# trackoon_solar.net
KiCad netlist of a schematic drawn in EAGLE
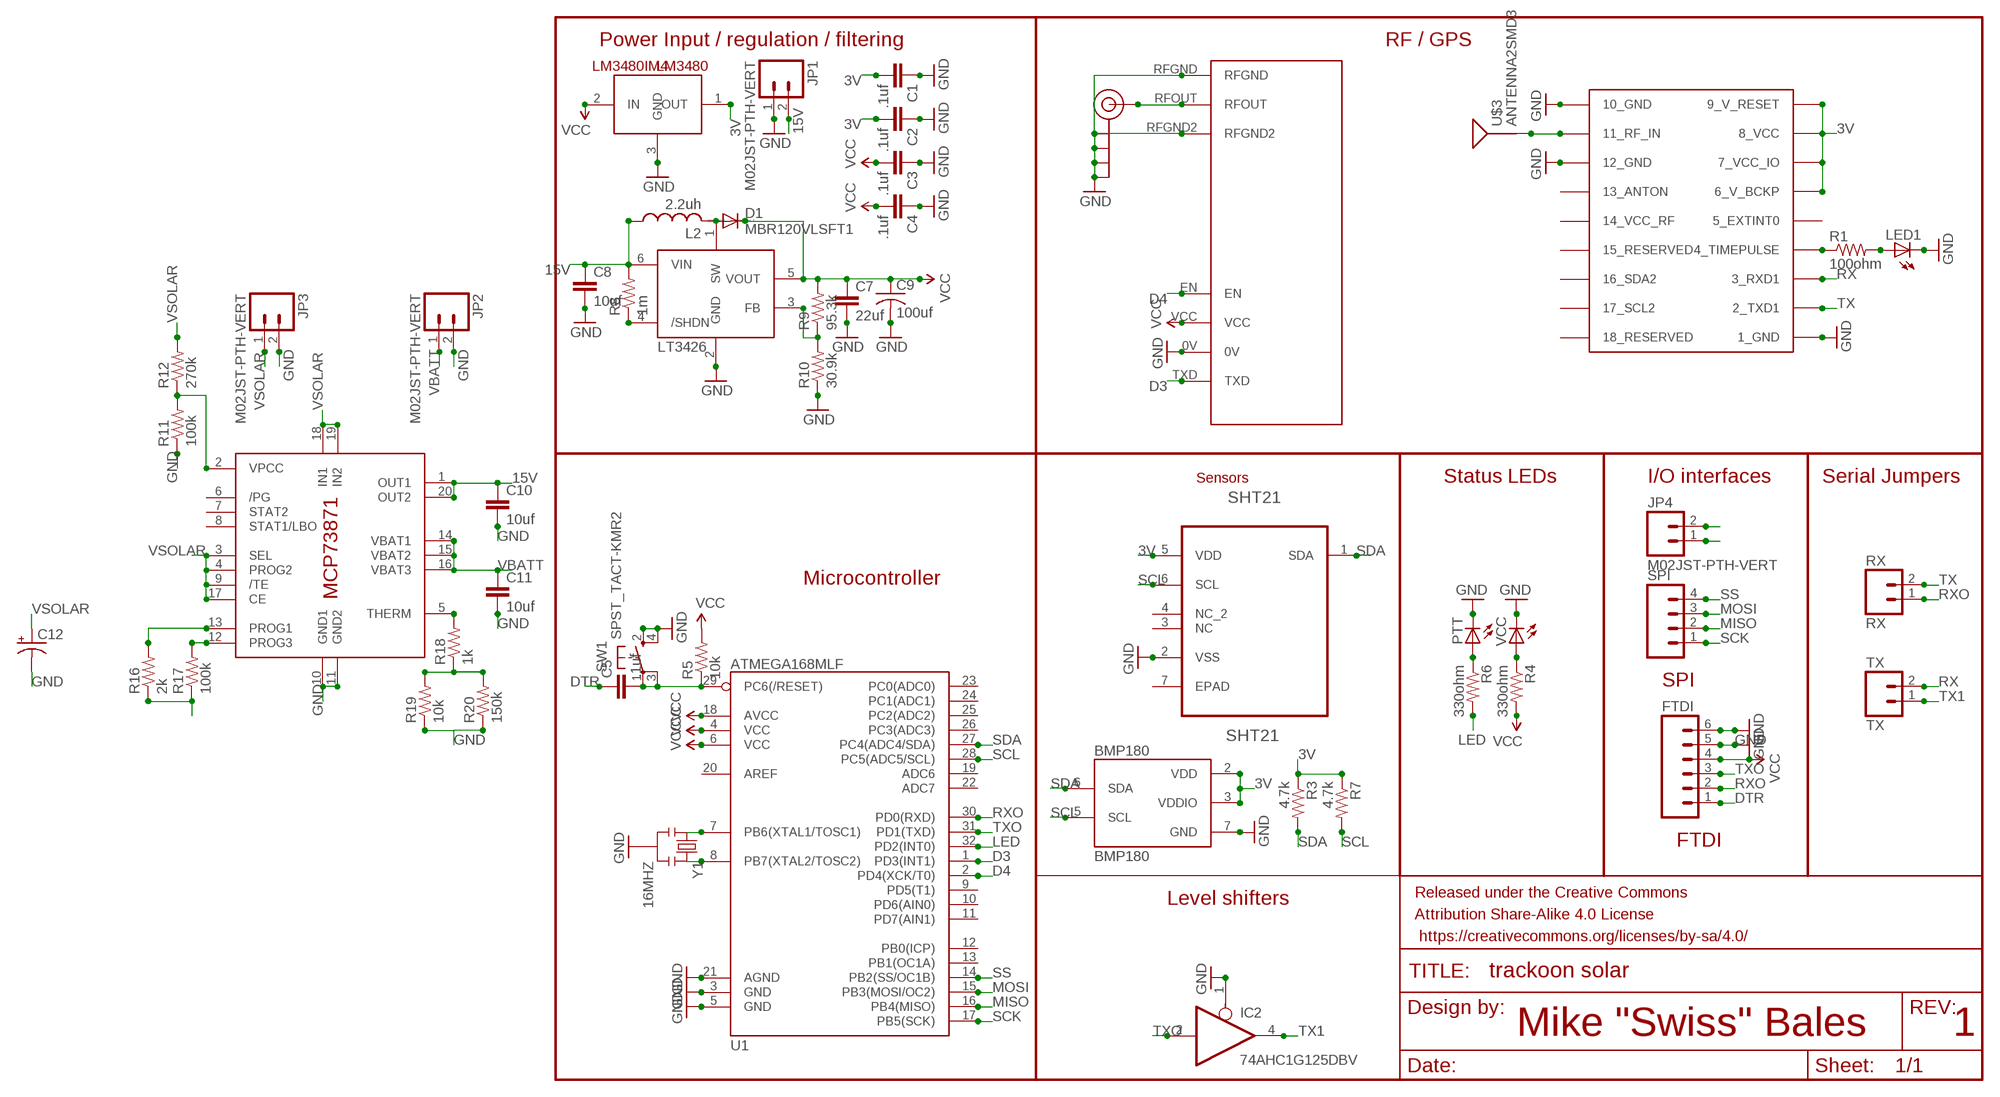
[diagram p0: schematic, sheet 1]

(export (version "E")
  (design (tool "Eeschema 10.0.6"))
  (components
    (comp (ref "BMP180")
      (value "BMP180")
      (footprint "eagle-import:BMP180")
      (libsource (lib "eagle-import") (part "BMP180"))
    )
    (comp (ref "C1")
      (value ".1uf")
      (footprint "eagle-import:0805")
      (libsource (lib "eagle-import") (part "CAP0805"))
    )
    (comp (ref "C2")
      (value ".1uf")
      (footprint "eagle-import:0805")
      (libsource (lib "eagle-import") (part "CAP0805"))
    )
    (comp (ref "C3")
      (value ".1uf")
      (footprint "eagle-import:0805")
      (libsource (lib "eagle-import") (part "CAP0805"))
    )
    (comp (ref "C4")
      (value ".1uf")
      (footprint "eagle-import:0805")
      (libsource (lib "eagle-import") (part "CAP0805"))
    )
    (comp (ref "C5")
      (value ".1uf")
      (footprint "eagle-import:0805")
      (libsource (lib "eagle-import") (part "CAP0805"))
    )
    (comp (ref "C7")
      (value "22uf")
      (footprint "eagle-import:0805")
      (libsource (lib "eagle-import") (part "CAP0805"))
    )
    (comp (ref "C8")
      (value "10uf")
      (footprint "eagle-import:0805")
      (libsource (lib "eagle-import") (part "CAP0805"))
    )
    (comp (ref "C9")
      (value "100uf")
      (footprint "eagle-import:C1206")
      (libsource (lib "eagle-import") (part "C-USC1206"))
    )
    (comp (ref "C10")
      (value "10uf")
      (footprint "eagle-import:0805")
      (libsource (lib "eagle-import") (part "CAP0805"))
    )
    (comp (ref "C11")
      (value "10uf")
      (footprint "eagle-import:0805")
      (libsource (lib "eagle-import") (part "CAP0805"))
    )
    (comp (ref "C12")
      (value "CPOL-US153CLV-1012")
      (footprint "eagle-import:153CLV-1012")
      (libsource (lib "eagle-import") (part "CPOL-US153CLV-1012"))
    )
    (comp (ref "D1")
      (value "MBR120VLSFT1")
      (footprint "eagle-import:SOD123")
      (libsource (lib "eagle-import") (part "DIODE-SOD123"))
    )
    (comp (ref "FRAME1")
      (value "FRAME-LETTER")
      (footprint "eagle-import:CREATIVE_COMMONS")
      (libsource (lib "eagle-import") (part "FRAME-LETTER"))
    )
    (comp (ref "FTDI")
      (value "M06NO_SILK_FEMALE_PTH")
      (footprint "eagle-import:1X06_NO_SILK")
      (libsource (lib "eagle-import") (part "M06NO_SILK_FEMALE_PTH"))
    )
    (comp (ref "IC1")
      (value "MCP73871")
      (footprint "eagle-import:QFN20")
      (libsource (lib "eagle-import") (part "MCP73871"))
    )
    (comp (ref "IC2")
      (value "74AHC1G125DBV")
      (footprint "eagle-import:SOT23-5")
      (libsource (lib "eagle-import") (part "741G125DBVAHC"))
    )
    (comp (ref "J$1")
      (value "SMA_EDGE")
      (footprint "eagle-import:SMA-EDGE")
      (libsource (lib "eagle-import") (part "SMA_EDGE"))
    )
    (comp (ref "JP1")
      (value "M02JST-PTH-VERT")
      (footprint "eagle-import:JST-2-PTH-VERT")
      (libsource (lib "eagle-import") (part "M02JST-PTH-VERT"))
    )
    (comp (ref "JP2")
      (value "M02JST-PTH-VERT")
      (footprint "eagle-import:JST-2-PTH-VERT")
      (libsource (lib "eagle-import") (part "M02JST-PTH-VERT"))
    )
    (comp (ref "JP3")
      (value "M02JST-PTH-VERT")
      (footprint "eagle-import:JST-2-PTH-VERT")
      (libsource (lib "eagle-import") (part "M02JST-PTH-VERT"))
    )
    (comp (ref "JP4")
      (value "M02JST-PTH-VERT")
      (footprint "eagle-import:JST-2-PTH-VERT")
      (libsource (lib "eagle-import") (part "M02JST-PTH-VERT"))
    )
    (comp (ref "L2")
      (value "2.2uh")
      (footprint "eagle-import:L1812")
      (libsource (lib "eagle-import") (part "L-USL1812"))
    )
    (comp (ref "LED1")
      (value "LEDCHIP-LED0805")
      (footprint "eagle-import:CHIP-LED0805")
      (libsource (lib "eagle-import") (part "LEDCHIP-LED0805"))
    )
    (comp (ref "LM3480")
      (value "LM3480IM4")
      (footprint "eagle-import:SOT23-3")
      (libsource (lib "eagle-import") (part "LM3480IM4"))
    )
    (comp (ref "LT3426")
      (value "LT3426")
      (footprint "eagle-import:SOT23-6")
      (libsource (lib "eagle-import") (part "LT3426"))
    )
    (comp (ref "PTT")
      (value "LEDCHIP-LED0805")
      (footprint "eagle-import:CHIP-LED0805")
      (libsource (lib "eagle-import") (part "LEDCHIP-LED0805"))
    )
    (comp (ref "R1")
      (value "100ohm")
      (footprint "eagle-import:0805")
      (libsource (lib "eagle-import") (part "RESISTOR0805-RES"))
    )
    (comp (ref "R3")
      (value "4.7k")
      (footprint "eagle-import:0805")
      (libsource (lib "eagle-import") (part "RESISTOR0805-RES"))
    )
    (comp (ref "R4")
      (value "330ohm")
      (footprint "eagle-import:0805")
      (libsource (lib "eagle-import") (part "RESISTOR0805-RES"))
    )
    (comp (ref "R5")
      (value "10k")
      (footprint "eagle-import:0805")
      (libsource (lib "eagle-import") (part "RESISTOR0805-RES"))
    )
    (comp (ref "R6")
      (value "330ohm")
      (footprint "eagle-import:0805")
      (libsource (lib "eagle-import") (part "RESISTOR0805-RES"))
    )
    (comp (ref "R7")
      (value "4.7k")
      (footprint "eagle-import:0805")
      (libsource (lib "eagle-import") (part "RESISTOR0805-RES"))
    )
    (comp (ref "R8")
      (value "1m")
      (footprint "eagle-import:0805")
      (libsource (lib "eagle-import") (part "RESISTOR0805-RES"))
    )
    (comp (ref "R9")
      (value "95.3k")
      (footprint "eagle-import:0805")
      (libsource (lib "eagle-import") (part "RESISTOR0805-RES"))
    )
    (comp (ref "R10")
      (value "30.9k")
      (footprint "eagle-import:0805")
      (libsource (lib "eagle-import") (part "RESISTOR0805-RES"))
    )
    (comp (ref "R11")
      (value "100k")
      (footprint "eagle-import:0805")
      (libsource (lib "eagle-import") (part "RESISTOR0805-RES"))
    )
    (comp (ref "R12")
      (value "270k")
      (footprint "eagle-import:0805")
      (libsource (lib "eagle-import") (part "RESISTOR0805-RES"))
    )
    (comp (ref "R16")
      (value "2k")
      (footprint "eagle-import:0805")
      (libsource (lib "eagle-import") (part "RESISTOR0805-RES"))
    )
    (comp (ref "R17")
      (value "100k")
      (footprint "eagle-import:0805")
      (libsource (lib "eagle-import") (part "RESISTOR0805-RES"))
    )
    (comp (ref "R18")
      (value "1k")
      (footprint "eagle-import:0805")
      (libsource (lib "eagle-import") (part "RESISTOR0805-RES"))
    )
    (comp (ref "R19")
      (value "10k")
      (footprint "eagle-import:0805")
      (libsource (lib "eagle-import") (part "RESISTOR0805-RES"))
    )
    (comp (ref "R20")
      (value "150k")
      (footprint "eagle-import:0805")
      (libsource (lib "eagle-import") (part "RESISTOR0805-RES"))
    )
    (comp (ref "RX")
      (value "RX")
      (footprint "eagle-import:1X02")
      (libsource (lib "eagle-import") (part "M02PTH"))
    )
    (comp (ref "SHT21")
      (value "SHT21")
      (footprint "eagle-import:DFN300X300X110-7N")
      (libsource (lib "eagle-import") (part "SHT21"))
    )
    (comp (ref "SPI")
      (value "M04JST-PTH-VERT")
      (footprint "eagle-import:JST-4-PTH-VERT")
      (libsource (lib "eagle-import") (part "M04JST-PTH-VERT"))
    )
    (comp (ref "SW1")
      (value "SPST_TACT-KMR2")
      (footprint "eagle-import:KMR2")
      (libsource (lib "eagle-import") (part "SPST_TACT-KMR2"))
    )
    (comp (ref "TX")
      (value "TX")
      (footprint "eagle-import:1X02")
      (libsource (lib "eagle-import") (part "M02PTH"))
    )
    (comp (ref "U$1")
      (value "UBLOX_MAX")
      (footprint "eagle-import:UBLOX_MAX")
      (libsource (lib "eagle-import") (part "UBLOX_MAX"))
    )
    (comp (ref "U$2")
      (value "RADIOMETRIX-HX1")
      (footprint "eagle-import:RADIOMETRIX-HX1")
      (libsource (lib "eagle-import") (part "RADIOMETRIX-HX1"))
    )
    (comp (ref "U$3")
      (value "ANTENNA2SMD3")
      (footprint "eagle-import:ANTENNA-CHIP4")
      (libsource (lib "eagle-import") (part "ANTENNA2SMD3"))
    )
    (comp (ref "U1")
      (value "ATMEGA168MLF")
      (footprint "eagle-import:MLF32")
      (libsource (lib "eagle-import") (part "ATMEGA168MLF"))
    )
    (comp (ref "VCC")
      (value "LEDCHIP-LED0805")
      (footprint "eagle-import:CHIP-LED0805")
      (libsource (lib "eagle-import") (part "LEDCHIP-LED0805"))
    )
    (comp (ref "Y1")
      (value "16MHZ")
      (footprint "eagle-import:RESONATOR-SMD")
      (libsource (lib "eagle-import") (part "RESONATOR16MHZ"))
    )
  )
  (nets
    (net (code "1") (name "/3V") (class "Default")
      (node (ref "BMP180") (pin "2") (pinfunction "VDD_2") (pintype "power_in"))
      (node (ref "BMP180") (pin "3") (pinfunction "VDDIO_3") (pintype "power_in"))
      (node (ref "C1") (pin "2") (pinfunction "2_2") (pintype "passive"))
      (node (ref "C2") (pin "2") (pinfunction "2_2") (pintype "passive"))
      (node (ref "LM3480") (pin "1") (pinfunction "OUT_1") (pintype "bidirectional"))
      (node (ref "R3") (pin "1") (pinfunction "1_1") (pintype "passive"))
      (node (ref "R7") (pin "1") (pinfunction "1_1") (pintype "passive"))
      (node (ref "SHT21") (pin "5") (pinfunction "VDD_5") (pintype "power_in"))
      (node (ref "U$1") (pin "6_V_BCKP") (pinfunction "6_V_BCKP_6_V_BCKP") (pintype "bidirectional"))
      (node (ref "U$1") (pin "7_VCC_IO") (pinfunction "7_VCC_IO_7_VCC_IO") (pintype "power_in"))
      (node (ref "U$1") (pin "8_VCC") (pinfunction "8_VCC_8_VCC") (pintype "power_in"))
      (node (ref "U$1") (pin "9_V_RESET") (pinfunction "9_V_RESET_9_V_RESET") (pintype "power_in"))
    )
    (net (code "2") (name "/15V") (class "Default")
      (node (ref "C10") (pin "1") (pinfunction "1_1") (pintype "passive"))
      (node (ref "C8") (pin "1") (pinfunction "1_1") (pintype "passive"))
      (node (ref "IC1") (pin "1") (pinfunction "OUT1_1") (pintype "output"))
      (node (ref "IC1") (pin "20") (pinfunction "OUT2_20") (pintype "output"))
      (node (ref "JP1") (pin "2") (pinfunction "2_2") (pintype "passive"))
      (node (ref "L2") (pin "1") (pinfunction "1_1") (pintype "passive"))
      (node (ref "LT3426") (pin "6") (pinfunction "VIN_6") (pintype "input"))
      (node (ref "R8") (pin "2") (pinfunction "2_2") (pintype "passive"))
    )
    (net (code "3") (name "/D3") (class "Default")
      (node (ref "U$2") (pin "TXD") (pinfunction "TXD_TXD") (pintype "bidirectional"))
      (node (ref "U1") (pin "1") (pinfunction "PD3(INT1)_1") (pintype "bidirectional"))
    )
    (net (code "4") (name "/D4") (class "Default")
      (node (ref "U$2") (pin "EN") (pinfunction "EN_EN") (pintype "bidirectional"))
      (node (ref "U1") (pin "2") (pinfunction "PD4(XCK/T0)_2") (pintype "bidirectional"))
    )
    (net (code "5") (name "/DTR") (class "Default")
      (node (ref "C5") (pin "1") (pinfunction "1_1") (pintype "passive"))
      (node (ref "FTDI") (pin "1") (pinfunction "1_1") (pintype "passive"))
    )
    (net (code "6") (name "/LED") (class "Default")
      (node (ref "R6") (pin "2") (pinfunction "2_2") (pintype "passive"))
      (node (ref "U1") (pin "32") (pinfunction "PD2(INT0)_32") (pintype "bidirectional"))
    )
    (net (code "7") (name "/MISO") (class "Default")
      (node (ref "SPI") (pin "2") (pinfunction "2_2") (pintype "passive"))
      (node (ref "U1") (pin "16") (pinfunction "PB4(MISO)_16") (pintype "bidirectional"))
    )
    (net (code "8") (name "/MOSI") (class "Default")
      (node (ref "SPI") (pin "3") (pinfunction "3_3") (pintype "passive"))
      (node (ref "U1") (pin "15") (pinfunction "PB3(MOSI/OC2)_15") (pintype "bidirectional"))
    )
    (net (code "9") (name "/RX") (class "Default")
      (node (ref "TX") (pin "2") (pinfunction "2_2") (pintype "passive"))
      (node (ref "U$1") (pin "3_RXD1") (pinfunction "3_RXD1_3_RXD1") (pintype "bidirectional"))
    )
    (net (code "10") (name "/RXO") (class "Default")
      (node (ref "FTDI") (pin "2") (pinfunction "2_2") (pintype "passive"))
      (node (ref "RX") (pin "1") (pinfunction "1_1") (pintype "passive"))
      (node (ref "U1") (pin "30") (pinfunction "PD0(RXD)_30") (pintype "bidirectional"))
    )
    (net (code "11") (name "/SCK") (class "Default")
      (node (ref "SPI") (pin "1") (pinfunction "1_1") (pintype "passive"))
      (node (ref "U1") (pin "17") (pinfunction "PB5(SCK)_17") (pintype "bidirectional"))
    )
    (net (code "12") (name "/SCL") (class "Default")
      (node (ref "BMP180") (pin "5") (pinfunction "SCL_5") (pintype "input"))
      (node (ref "JP4") (pin "1") (pinfunction "1_1") (pintype "passive"))
      (node (ref "R7") (pin "2") (pinfunction "2_2") (pintype "passive"))
      (node (ref "SHT21") (pin "6") (pinfunction "SCL_6") (pintype "input"))
      (node (ref "U1") (pin "28") (pinfunction "PC5(ADC5/SCL)_28") (pintype "bidirectional"))
    )
    (net (code "13") (name "/SDA") (class "Default")
      (node (ref "BMP180") (pin "6") (pinfunction "SDA_6") (pintype "bidirectional"))
      (node (ref "JP4") (pin "2") (pinfunction "2_2") (pintype "passive"))
      (node (ref "R3") (pin "2") (pinfunction "2_2") (pintype "passive"))
      (node (ref "SHT21") (pin "1") (pinfunction "SDA_1") (pintype "bidirectional"))
      (node (ref "U1") (pin "27") (pinfunction "PC4(ADC4/SDA)_27") (pintype "bidirectional"))
    )
    (net (code "14") (name "/SS") (class "Default")
      (node (ref "SPI") (pin "4") (pinfunction "4_4") (pintype "passive"))
      (node (ref "U1") (pin "14") (pinfunction "PB2(SS/OC1B)_14") (pintype "bidirectional"))
    )
    (net (code "15") (name "/TX") (class "Default")
      (node (ref "RX") (pin "2") (pinfunction "2_2") (pintype "passive"))
      (node (ref "U$1") (pin "2_TXD1") (pinfunction "2_TXD1_2_TXD1") (pintype "bidirectional"))
    )
    (net (code "16") (name "/TX1") (class "Default")
      (node (ref "IC2") (pin "4") (pinfunction "O_4") (pintype "tri_state"))
      (node (ref "TX") (pin "1") (pinfunction "1_1") (pintype "passive"))
    )
    (net (code "17") (name "/TXO") (class "Default")
      (node (ref "FTDI") (pin "3") (pinfunction "3_3") (pintype "passive"))
      (node (ref "IC2") (pin "2") (pinfunction "I_2") (pintype "input"))
      (node (ref "U1") (pin "31") (pinfunction "PD1(TXD)_31") (pintype "bidirectional"))
    )
    (net (code "18") (name "/VBATT") (class "Default")
      (node (ref "C11") (pin "1") (pinfunction "1_1") (pintype "passive"))
      (node (ref "IC1") (pin "14") (pinfunction "VBAT1_14") (pintype "output"))
      (node (ref "IC1") (pin "15") (pinfunction "VBAT2_15") (pintype "output"))
      (node (ref "IC1") (pin "16") (pinfunction "VBAT3_16") (pintype "output"))
      (node (ref "JP2") (pin "1") (pinfunction "1_1") (pintype "passive"))
    )
    (net (code "19") (name "/VSOLAR") (class "Default")
      (node (ref "C12") (pin "+") (pinfunction "+_+") (pintype "passive"))
      (node (ref "IC1") (pin "17") (pinfunction "CE_17") (pintype "input"))
      (node (ref "IC1") (pin "18") (pinfunction "IN1_18") (pintype "input"))
      (node (ref "IC1") (pin "19") (pinfunction "IN2_19") (pintype "input"))
      (node (ref "IC1") (pin "3") (pinfunction "SEL_3") (pintype "input"))
      (node (ref "IC1") (pin "4") (pinfunction "PROG2_4") (pintype "input"))
      (node (ref "IC1") (pin "9") (pinfunction "/TE_9") (pintype "input"))
      (node (ref "JP3") (pin "1") (pinfunction "1_1") (pintype "passive"))
      (node (ref "R12") (pin "2") (pinfunction "2_2") (pintype "passive"))
    )
    (net (code "20") (name "GND") (class "Default")
      (node (ref "BMP180") (pin "7") (pinfunction "GND_7") (pintype "power_in"))
      (node (ref "C1") (pin "1") (pinfunction "1_1") (pintype "passive"))
      (node (ref "C10") (pin "2") (pinfunction "2_2") (pintype "passive"))
      (node (ref "C11") (pin "2") (pinfunction "2_2") (pintype "passive"))
      (node (ref "C12") (pin "-") (pinfunction "-_-") (pintype "passive"))
      (node (ref "C2") (pin "1") (pinfunction "1_1") (pintype "passive"))
      (node (ref "C3") (pin "1") (pinfunction "1_1") (pintype "passive"))
      (node (ref "C4") (pin "1") (pinfunction "1_1") (pintype "passive"))
      (node (ref "C7") (pin "2") (pinfunction "2_2") (pintype "passive"))
      (node (ref "C8") (pin "2") (pinfunction "2_2") (pintype "passive"))
      (node (ref "C9") (pin "2") (pinfunction "2_2") (pintype "passive"))
      (node (ref "FTDI") (pin "5") (pinfunction "5_5") (pintype "passive"))
      (node (ref "FTDI") (pin "6") (pinfunction "6_6") (pintype "passive"))
      (node (ref "IC1") (pin "10") (pinfunction "GND1_10") (pintype "power_in"))
      (node (ref "IC1") (pin "11") (pinfunction "GND2_11") (pintype "power_in"))
      (node (ref "IC2") (pin "1") (pinfunction "OE_1") (pintype "input"))
      (node (ref "J$1") (pin "GND@0") (pinfunction "GND_GND@0") (pintype "bidirectional"))
      (node (ref "J$1") (pin "GND@1") (pinfunction "GND_GND@1") (pintype "bidirectional"))
      (node (ref "J$1") (pin "GND@2") (pinfunction "GND_GND@2") (pintype "bidirectional"))
      (node (ref "J$1") (pin "GND@3") (pinfunction "GND_GND@3") (pintype "bidirectional"))
      (node (ref "JP1") (pin "1") (pinfunction "1_1") (pintype "passive"))
      (node (ref "JP2") (pin "2") (pinfunction "2_2") (pintype "passive"))
      (node (ref "JP3") (pin "2") (pinfunction "2_2") (pintype "passive"))
      (node (ref "LED1") (pin "C") (pinfunction "C_C") (pintype "passive"))
      (node (ref "LM3480") (pin "3") (pinfunction "GND_3") (pintype "bidirectional"))
      (node (ref "LT3426") (pin "2") (pinfunction "GND_2") (pintype "power_in"))
      (node (ref "PTT") (pin "C") (pinfunction "C_C") (pintype "passive"))
      (node (ref "R10") (pin "1") (pinfunction "1_1") (pintype "passive"))
      (node (ref "R11") (pin "1") (pinfunction "1_1") (pintype "passive"))
      (node (ref "R16") (pin "1") (pinfunction "1_1") (pintype "passive"))
      (node (ref "R17") (pin "1") (pinfunction "1_1") (pintype "passive"))
      (node (ref "R19") (pin "1") (pinfunction "1_1") (pintype "passive"))
      (node (ref "R20") (pin "1") (pinfunction "1_1") (pintype "passive"))
      (node (ref "SHT21") (pin "2") (pinfunction "VSS_2") (pintype "power_in"))
      (node (ref "SW1") (pin "2") (pinfunction "S_2") (pintype "passive"))
      (node (ref "SW1") (pin "4") (pinfunction "S1_4") (pintype "passive"))
      (node (ref "U$1") (pin "10_GND") (pinfunction "10_GND_10_GND") (pintype "power_in"))
      (node (ref "U$1") (pin "12_GND") (pinfunction "12_GND_12_GND") (pintype "power_in"))
      (node (ref "U$1") (pin "1_GND") (pinfunction "1_GND_1_GND") (pintype "power_in"))
      (node (ref "U$2") (pin "0V") (pinfunction "0V_0V") (pintype "bidirectional"))
      (node (ref "U$2") (pin "RFGND") (pinfunction "RFGND_RFGND") (pintype "bidirectional"))
      (node (ref "U$2") (pin "RFGND2") (pinfunction "RFGND2_RFGND2") (pintype "bidirectional"))
      (node (ref "U1") (pin "21") (pinfunction "AGND_21") (pintype "bidirectional"))
      (node (ref "U1") (pin "3") (pinfunction "GND_3") (pintype "bidirectional"))
      (node (ref "U1") (pin "5") (pinfunction "GND_5") (pintype "bidirectional"))
      (node (ref "VCC") (pin "C") (pinfunction "C_C") (pintype "passive"))
      (node (ref "Y1") (pin "2") (pinfunction "2_2") (pintype "passive"))
    )
    (net (code "21") (name "Net-(IC1-PROG1)") (class "Default")
      (node (ref "IC1") (pin "13") (pinfunction "PROG1_13") (pintype "input"))
      (node (ref "R16") (pin "2") (pinfunction "2_2") (pintype "passive"))
    )
    (net (code "22") (name "Net-(IC1-PROG3)") (class "Default")
      (node (ref "IC1") (pin "12") (pinfunction "PROG3_12") (pintype "input"))
      (node (ref "R17") (pin "2") (pinfunction "2_2") (pintype "passive"))
    )
    (net (code "23") (name "Net-(IC1-THERM)") (class "Default")
      (node (ref "IC1") (pin "5") (pinfunction "THERM_5") (pintype "input"))
      (node (ref "R18") (pin "2") (pinfunction "2_2") (pintype "passive"))
    )
    (net (code "24") (name "Net-(IC1-VPCC)") (class "Default")
      (node (ref "IC1") (pin "2") (pinfunction "VPCC_2") (pintype "input"))
      (node (ref "R11") (pin "2") (pinfunction "2_2") (pintype "passive"))
      (node (ref "R12") (pin "1") (pinfunction "1_1") (pintype "passive"))
    )
    (net (code "25") (name "Net-(J$1-SIGNAL)") (class "Default")
      (node (ref "J$1") (pin "SIG") (pinfunction "SIGNAL_SIG") (pintype "bidirectional"))
      (node (ref "U$2") (pin "RFOUT") (pinfunction "RFOUT_RFOUT") (pintype "bidirectional"))
    )
    (net (code "26") (name "Net-(LED1-PadA)") (class "Default")
      (node (ref "LED1") (pin "A") (pinfunction "A_A") (pintype "passive"))
      (node (ref "R1") (pin "2") (pinfunction "2_2") (pintype "passive"))
    )
    (net (code "27") (name "Net-(LT3426-FB)") (class "Default")
      (node (ref "LT3426") (pin "3") (pinfunction "FB_3") (pintype "input"))
      (node (ref "R10") (pin "2") (pinfunction "2_2") (pintype "passive"))
      (node (ref "R9") (pin "1") (pinfunction "1_1") (pintype "passive"))
    )
    (net (code "28") (name "Net-(LT3426-SW)") (class "Default")
      (node (ref "D1") (pin "A") (pinfunction "A_A") (pintype "passive"))
      (node (ref "L2") (pin "2") (pinfunction "2_2") (pintype "passive"))
      (node (ref "LT3426") (pin "1") (pinfunction "SW_1") (pintype "output"))
    )
    (net (code "29") (name "Net-(LT3426-{slash}SHDN)") (class "Default")
      (node (ref "LT3426") (pin "4") (pinfunction "/SHDN_4") (pintype "input"))
      (node (ref "R8") (pin "1") (pinfunction "1_1") (pintype "passive"))
    )
    (net (code "30") (name "Net-(PTT-PadA)") (class "Default")
      (node (ref "PTT") (pin "A") (pinfunction "A_A") (pintype "passive"))
      (node (ref "R6") (pin "1") (pinfunction "1_1") (pintype "passive"))
    )
    (net (code "31") (name "Net-(R1-Pad1)") (class "Default")
      (node (ref "R1") (pin "1") (pinfunction "1_1") (pintype "passive"))
      (node (ref "U$1") (pin "4_TIMEPULSE") (pinfunction "4_TIMEPULSE_4_TIMEPULSE") (pintype "bidirectional"))
    )
    (net (code "32") (name "Net-(R4-Pad1)") (class "Default")
      (node (ref "R4") (pin "1") (pinfunction "1_1") (pintype "passive"))
      (node (ref "VCC") (pin "A") (pinfunction "A_A") (pintype "passive"))
    )
    (net (code "33") (name "Net-(R18-Pad1)") (class "Default")
      (node (ref "R18") (pin "1") (pinfunction "1_1") (pintype "passive"))
      (node (ref "R19") (pin "2") (pinfunction "2_2") (pintype "passive"))
      (node (ref "R20") (pin "2") (pinfunction "2_2") (pintype "passive"))
    )
    (net (code "34") (name "Net-(SW1-P)") (class "Default")
      (node (ref "C5") (pin "2") (pinfunction "2_2") (pintype "passive"))
      (node (ref "R5") (pin "1") (pinfunction "1_1") (pintype "passive"))
      (node (ref "SW1") (pin "1") (pinfunction "P_1") (pintype "passive"))
      (node (ref "SW1") (pin "3") (pinfunction "P1_3") (pintype "passive"))
      (node (ref "U1") (pin "29") (pinfunction "PC6(/RESET)_29") (pintype "bidirectional"))
    )
    (net (code "35") (name "Net-(U$3-SIGNAL)") (class "Default")
      (node (ref "U$1") (pin "11_RF_IN") (pinfunction "11_RF_IN_11_RF_IN") (pintype "bidirectional"))
      (node (ref "U$3") (pin "SIG") (pinfunction "SIGNAL_SIG") (pintype "bidirectional"))
    )
    (net (code "36") (name "Net-(U1-PB6(XTAL1{slash}TOSC1))") (class "Default")
      (node (ref "U1") (pin "7") (pinfunction "PB6(XTAL1/TOSC1)_7") (pintype "bidirectional"))
      (node (ref "Y1") (pin "1") (pinfunction "1_1") (pintype "passive"))
    )
    (net (code "37") (name "Net-(U1-PB7(XTAL2{slash}TOSC2))") (class "Default")
      (node (ref "U1") (pin "8") (pinfunction "PB7(XTAL2/TOSC2)_8") (pintype "bidirectional"))
      (node (ref "Y1") (pin "3") (pinfunction "3_3") (pintype "passive"))
    )
    (net (code "38") (name "VCC") (class "Default")
      (node (ref "C3") (pin "2") (pinfunction "2_2") (pintype "passive"))
      (node (ref "C4") (pin "2") (pinfunction "2_2") (pintype "passive"))
      (node (ref "C7") (pin "1") (pinfunction "1_1") (pintype "passive"))
      (node (ref "C9") (pin "1") (pinfunction "1_1") (pintype "passive"))
      (node (ref "D1") (pin "C") (pinfunction "C_C") (pintype "passive"))
      (node (ref "FTDI") (pin "4") (pinfunction "4_4") (pintype "passive"))
      (node (ref "LM3480") (pin "2") (pinfunction "IN_2") (pintype "bidirectional"))
      (node (ref "LT3426") (pin "5") (pinfunction "VOUT_5") (pintype "output"))
      (node (ref "R4") (pin "2") (pinfunction "2_2") (pintype "passive"))
      (node (ref "R5") (pin "2") (pinfunction "2_2") (pintype "passive"))
      (node (ref "R9") (pin "2") (pinfunction "2_2") (pintype "passive"))
      (node (ref "U$2") (pin "VCC") (pinfunction "VCC_VCC") (pintype "bidirectional"))
      (node (ref "U1") (pin "18") (pinfunction "AVCC_18") (pintype "bidirectional"))
      (node (ref "U1") (pin "4") (pinfunction "VCC_4") (pintype "bidirectional"))
      (node (ref "U1") (pin "6") (pinfunction "VCC_6") (pintype "bidirectional"))
    )
    (net (code "39") (name "unconnected-(IC1-STAT1{slash}LBO-Pad8)") (class "Default")
      (node (ref "IC1") (pin "8") (pinfunction "STAT1/LBO_8") (pintype "output"))
    )
    (net (code "40") (name "unconnected-(IC1-STAT2-Pad7)") (class "Default")
      (node (ref "IC1") (pin "7") (pinfunction "STAT2_7") (pintype "output"))
    )
    (net (code "41") (name "unconnected-(IC1-{slash}PG-Pad6)") (class "Default")
      (node (ref "IC1") (pin "6") (pinfunction "/PG_6") (pintype "output"))
    )
    (net (code "42") (name "unconnected-(SHT21-EPAD-Pad7)") (class "Default")
      (node (ref "SHT21") (pin "7") (pinfunction "EPAD_7") (pintype "passive"))
    )
    (net (code "43") (name "unconnected-(SHT21-NC-Pad3)") (class "Default")
      (node (ref "SHT21") (pin "3") (pinfunction "NC_3") (pintype "no_connect"))
    )
    (net (code "44") (name "unconnected-(SHT21-NC_2-Pad4)") (class "Default")
      (node (ref "SHT21") (pin "4") (pinfunction "NC_2_4") (pintype "no_connect"))
    )
    (net (code "45") (name "unconnected-(U$1-Pad5_EXTINT0)") (class "Default")
      (node (ref "U$1") (pin "5_EXTINT0") (pinfunction "5_EXTINT0_5_EXTINT0") (pintype "bidirectional"))
    )
    (net (code "46") (name "unconnected-(U$1-Pad13_ANTON)") (class "Default")
      (node (ref "U$1") (pin "13_ANTON") (pinfunction "13_ANTON_13_ANTON") (pintype "bidirectional"))
    )
    (net (code "47") (name "unconnected-(U$1-Pad14_VCC_RF)") (class "Default")
      (node (ref "U$1") (pin "14_VCC_RF") (pinfunction "14_VCC_RF_14_VCC_RF") (pintype "bidirectional"))
    )
    (net (code "48") (name "unconnected-(U$1-Pad15_RESERVED)") (class "Default")
      (node (ref "U$1") (pin "15_RESERVED") (pinfunction "15_RESERVED_15_RESERVED") (pintype "bidirectional"))
    )
    (net (code "49") (name "unconnected-(U$1-Pad16_SDA2)") (class "Default")
      (node (ref "U$1") (pin "16_SDA2") (pinfunction "16_SDA2_16_SDA2") (pintype "bidirectional"))
    )
    (net (code "50") (name "unconnected-(U$1-Pad17_SCL2)") (class "Default")
      (node (ref "U$1") (pin "17_SCL2") (pinfunction "17_SCL2_17_SCL2") (pintype "bidirectional"))
    )
    (net (code "51") (name "unconnected-(U$1-Pad18_RESERVED)") (class "Default")
      (node (ref "U$1") (pin "18_RESERVED") (pinfunction "18_RESERVED_18_RESERVED") (pintype "bidirectional"))
    )
    (net (code "52") (name "unconnected-(U1-ADC6-Pad19)") (class "Default")
      (node (ref "U1") (pin "19") (pinfunction "ADC6_19") (pintype "bidirectional"))
    )
    (net (code "53") (name "unconnected-(U1-ADC7-Pad22)") (class "Default")
      (node (ref "U1") (pin "22") (pinfunction "ADC7_22") (pintype "bidirectional"))
    )
    (net (code "54") (name "unconnected-(U1-AREF-Pad20)") (class "Default")
      (node (ref "U1") (pin "20") (pinfunction "AREF_20") (pintype "bidirectional"))
    )
    (net (code "55") (name "unconnected-(U1-PB0(ICP)-Pad12)") (class "Default")
      (node (ref "U1") (pin "12") (pinfunction "PB0(ICP)_12") (pintype "bidirectional"))
    )
    (net (code "56") (name "unconnected-(U1-PB1(OC1A)-Pad13)") (class "Default")
      (node (ref "U1") (pin "13") (pinfunction "PB1(OC1A)_13") (pintype "bidirectional"))
    )
    (net (code "57") (name "unconnected-(U1-PC0(ADC0)-Pad23)") (class "Default")
      (node (ref "U1") (pin "23") (pinfunction "PC0(ADC0)_23") (pintype "bidirectional"))
    )
    (net (code "58") (name "unconnected-(U1-PC1(ADC1)-Pad24)") (class "Default")
      (node (ref "U1") (pin "24") (pinfunction "PC1(ADC1)_24") (pintype "bidirectional"))
    )
    (net (code "59") (name "unconnected-(U1-PC2(ADC2)-Pad25)") (class "Default")
      (node (ref "U1") (pin "25") (pinfunction "PC2(ADC2)_25") (pintype "bidirectional"))
    )
    (net (code "60") (name "unconnected-(U1-PC3(ADC3)-Pad26)") (class "Default")
      (node (ref "U1") (pin "26") (pinfunction "PC3(ADC3)_26") (pintype "bidirectional"))
    )
    (net (code "61") (name "unconnected-(U1-PD5(T1)-Pad9)") (class "Default")
      (node (ref "U1") (pin "9") (pinfunction "PD5(T1)_9") (pintype "bidirectional"))
    )
    (net (code "62") (name "unconnected-(U1-PD6(AIN0)-Pad10)") (class "Default")
      (node (ref "U1") (pin "10") (pinfunction "PD6(AIN0)_10") (pintype "bidirectional"))
    )
    (net (code "63") (name "unconnected-(U1-PD7(AIN1)-Pad11)") (class "Default")
      (node (ref "U1") (pin "11") (pinfunction "PD7(AIN1)_11") (pintype "bidirectional"))
    )
  )
)
